# Isolation.net
KiCad netlist of a schematic drawn in Altium Designer
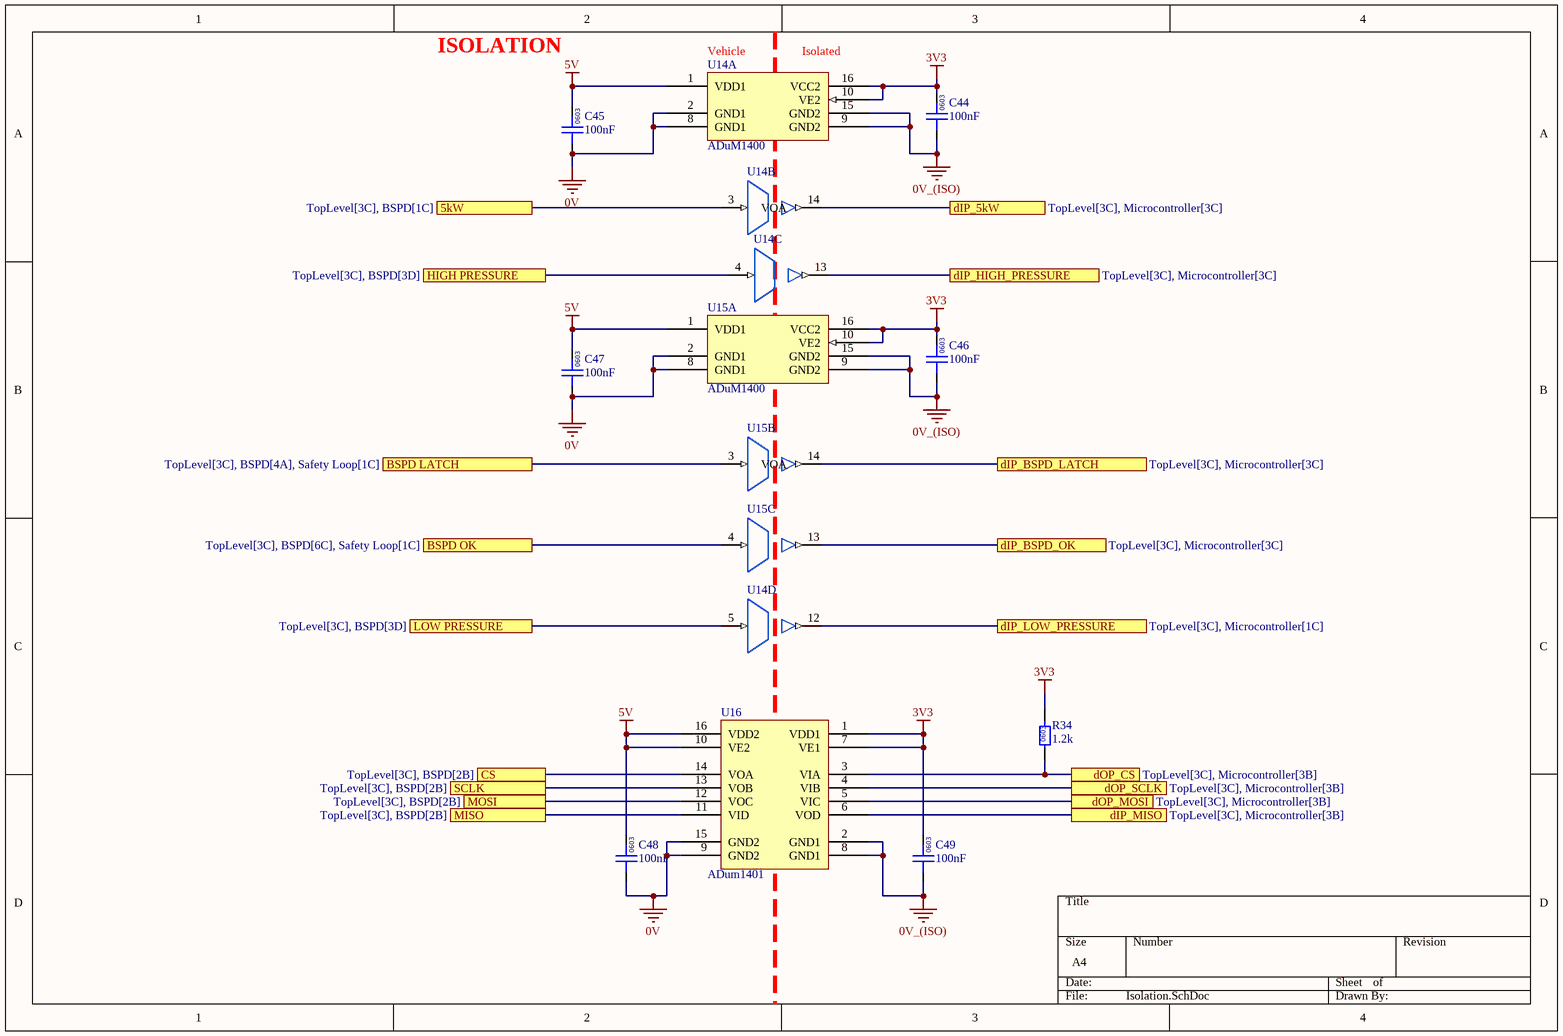
[diagram p0: Isolation.SchDoc]

(export (version "E")
  (design (tool "Eeschema 10.0.6"))
  (components
    (comp (ref "C44")
      (value "100nF")
      (footprint "0603")
      (fields
        (field (name "PART NUMBER") "GCM188L81H104KA57D")
        (field (name "MANUFACTURER") "muRata")
        (field (name "TOLERANCE") "±10%")
      )
      (libsource (lib "ts_standard_library") (part "Capacitor 0603"))
    )
    (comp (ref "C45")
      (value "100nF")
      (footprint "0603")
      (fields
        (field (name "PART NUMBER") "GCM188L81H104KA57D")
        (field (name "MANUFACTURER") "muRata")
        (field (name "TOLERANCE") "±10%")
      )
      (libsource (lib "ts_standard_library") (part "Capacitor 0603"))
    )
    (comp (ref "C46")
      (value "100nF")
      (footprint "0603")
      (fields
        (field (name "PART NUMBER") "GCM188L81H104KA57D")
        (field (name "MANUFACTURER") "muRata")
        (field (name "TOLERANCE") "±10%")
      )
      (libsource (lib "ts_standard_library") (part "Capacitor 0603"))
    )
    (comp (ref "C47")
      (value "100nF")
      (footprint "0603")
      (fields
        (field (name "PART NUMBER") "GCM188L81H104KA57D")
        (field (name "MANUFACTURER") "muRata")
        (field (name "TOLERANCE") "±10%")
      )
      (libsource (lib "ts_standard_library") (part "Capacitor 0603"))
    )
    (comp (ref "C48")
      (value "100nF")
      (footprint "0603")
      (fields
        (field (name "PART NUMBER") "GCM188L81H104KA57D")
        (field (name "MANUFACTURER") "muRata")
        (field (name "TOLERANCE") "±10%")
      )
      (libsource (lib "ts_standard_library") (part "Capacitor 0603"))
    )
    (comp (ref "C49")
      (value "100nF")
      (footprint "0603")
      (fields
        (field (name "PART NUMBER") "GCM188L81H104KA57D")
        (field (name "MANUFACTURER") "muRata")
        (field (name "TOLERANCE") "±10%")
      )
      (libsource (lib "ts_standard_library") (part "Capacitor 0603"))
    )
    (comp (ref "R34")
      (value "1.2k")
      (footprint "0603")
      (fields
        (field (name "PART NUMBER") "RC0603JR-071K2L")
        (field (name "MANUFACTURER") "YAGEO")
        (field (name "TOLERANCE") "0.01")
      )
      (libsource (lib "ts_standard_library") (part "Resistor 0603"))
    )
    (comp (ref "U14")
      (value "ADuM1400")
      (footprint "AD 16-SOIC")
      (fields
        (field (name "MANUFACTURER") "Analog Devices")
        (field (name "DIGIKEY PART NUMBER") "ADUM1400WSRWZ-ND")
      )
      (libsource (lib "ts_standard_library") (part "ADuM1400"))
    )
    (comp (ref "U15")
      (value "ADuM1400")
      (footprint "AD 16-SOIC")
      (fields
        (field (name "MANUFACTURER") "Analog Devices")
        (field (name "DIGIKEY PART NUMBER") "ADUM1400WSRWZ-ND")
      )
      (libsource (lib "ts_standard_library") (part "ADuM1400"))
    )
    (comp (ref "U16")
      (value "ADum1401")
      (footprint "AD 16-SOIC")
      (fields (field (name "PART NUMBER") "ADuM1401") (field (name "MANUFACTURER") "Analog Devices"))
      (libsource (lib "ts_standard_library") (part "ADum1401"))
    )
  )
  (nets
    (net (code "1") (name "/5kW") (class "Default")
      (node (ref "U14") (pin "3") (pinfunction "VIA_3") (pintype "input"))
    )
    (net (code "2") (name "/BSPD LATCH") (class "Default")
      (node (ref "U15") (pin "3") (pinfunction "VIA_3") (pintype "input"))
    )
    (net (code "3") (name "/BSPD OK") (class "Default")
      (node (ref "U15") (pin "4") (pinfunction "VIB_4") (pintype "input"))
    )
    (net (code "4") (name "/CS") (class "Default")
      (node (ref "U16") (pin "14") (pinfunction "VOA_14") (pintype "passive"))
    )
    (net (code "5") (name "/HIGH PRESSURE") (class "Default")
      (node (ref "U14") (pin "4") (pinfunction "VIB_4") (pintype "input"))
    )
    (net (code "6") (name "/LOW PRESSURE") (class "Default")
      (node (ref "U14") (pin "5") (pinfunction "VIC_5") (pintype "input"))
    )
    (net (code "7") (name "/MISO") (class "Default")
      (node (ref "U16") (pin "11") (pinfunction "VID_11") (pintype "passive"))
    )
    (net (code "8") (name "/MOSI") (class "Default")
      (node (ref "U16") (pin "12") (pinfunction "VOC_12") (pintype "passive"))
    )
    (net (code "9") (name "/SCLK") (class "Default")
      (node (ref "U16") (pin "13") (pinfunction "VOB_13") (pintype "passive"))
    )
    (net (code "10") (name "/dIP_5kW") (class "Default")
      (node (ref "U14") (pin "14") (pinfunction "VOA_14") (pintype "output"))
    )
    (net (code "11") (name "/dIP_BSPD_LATCH") (class "Default")
      (node (ref "U15") (pin "14") (pinfunction "VOA_14") (pintype "output"))
    )
    (net (code "12") (name "/dIP_BSPD_OK") (class "Default")
      (node (ref "U15") (pin "13") (pinfunction "VOB_13") (pintype "output"))
    )
    (net (code "13") (name "/dIP_HIGH_PRESSURE") (class "Default")
      (node (ref "U14") (pin "13") (pinfunction "VOB_13") (pintype "output"))
    )
    (net (code "14") (name "/dIP_LOW_PRESSURE") (class "Default")
      (node (ref "U14") (pin "12") (pinfunction "VOC_12") (pintype "output"))
    )
    (net (code "15") (name "/dIP_MISO") (class "Default")
      (node (ref "U16") (pin "6") (pinfunction "VOD_6") (pintype "passive"))
    )
    (net (code "16") (name "/dOP_CS") (class "Default")
      (node (ref "R34") (pin "1") (pinfunction "1_1") (pintype "passive"))
      (node (ref "U16") (pin "3") (pinfunction "VIA_3") (pintype "passive"))
    )
    (net (code "17") (name "/dOP_MOSI") (class "Default")
      (node (ref "U16") (pin "5") (pinfunction "VIC_5") (pintype "passive"))
    )
    (net (code "18") (name "/dOP_SCLK") (class "Default")
      (node (ref "U16") (pin "4") (pinfunction "VIB_4") (pintype "passive"))
    )
    (net (code "19") (name "0V") (class "Default")
      (node (ref "C45") (pin "1") (pinfunction "1_1") (pintype "passive"))
      (node (ref "C47") (pin "1") (pinfunction "1_1") (pintype "passive"))
      (node (ref "C48") (pin "1") (pinfunction "1_1") (pintype "passive"))
      (node (ref "U14") (pin "2") (pinfunction "GND1_2") (pintype "power_in"))
      (node (ref "U14") (pin "8") (pinfunction "GND1_8") (pintype "power_in"))
      (node (ref "U15") (pin "2") (pinfunction "GND1_2") (pintype "power_in"))
      (node (ref "U15") (pin "8") (pinfunction "GND1_8") (pintype "power_in"))
      (node (ref "U16") (pin "15") (pinfunction "GND2_15") (pintype "passive"))
      (node (ref "U16") (pin "9") (pinfunction "GND2_9") (pintype "passive"))
    )
    (net (code "20") (name "0V_(ISO)") (class "Default")
      (node (ref "C44") (pin "1") (pinfunction "1_1") (pintype "passive"))
      (node (ref "C46") (pin "1") (pinfunction "1_1") (pintype "passive"))
      (node (ref "C49") (pin "1") (pinfunction "1_1") (pintype "passive"))
      (node (ref "U14") (pin "15") (pinfunction "GND2_15") (pintype "power_in"))
      (node (ref "U14") (pin "9") (pinfunction "GND2_9") (pintype "power_in"))
      (node (ref "U15") (pin "15") (pinfunction "GND2_15") (pintype "power_in"))
      (node (ref "U15") (pin "9") (pinfunction "GND2_9") (pintype "power_in"))
      (node (ref "U16") (pin "2") (pinfunction "GND1_2") (pintype "passive"))
      (node (ref "U16") (pin "8") (pinfunction "GND1_8") (pintype "passive"))
    )
    (net (code "21") (name "3V3") (class "Default")
      (node (ref "C44") (pin "2") (pinfunction "2_2") (pintype "passive"))
      (node (ref "C46") (pin "2") (pinfunction "2_2") (pintype "passive"))
      (node (ref "C49") (pin "2") (pinfunction "2_2") (pintype "passive"))
      (node (ref "R34") (pin "2") (pinfunction "2_2") (pintype "passive"))
      (node (ref "U14") (pin "10") (pinfunction "VE2_10") (pintype "input"))
      (node (ref "U14") (pin "16") (pinfunction "VCC2_16") (pintype "power_in"))
      (node (ref "U15") (pin "10") (pinfunction "VE2_10") (pintype "input"))
      (node (ref "U15") (pin "16") (pinfunction "VCC2_16") (pintype "power_in"))
      (node (ref "U16") (pin "1") (pinfunction "VDD1_1") (pintype "passive"))
      (node (ref "U16") (pin "7") (pinfunction "VE1_7") (pintype "passive"))
    )
    (net (code "22") (name "5V") (class "Default")
      (node (ref "C45") (pin "2") (pinfunction "2_2") (pintype "passive"))
      (node (ref "C47") (pin "2") (pinfunction "2_2") (pintype "passive"))
      (node (ref "C48") (pin "2") (pinfunction "2_2") (pintype "passive"))
      (node (ref "U14") (pin "1") (pinfunction "VDD1_1") (pintype "power_in"))
      (node (ref "U15") (pin "1") (pinfunction "VDD1_1") (pintype "power_in"))
      (node (ref "U16") (pin "10") (pinfunction "VE2_10") (pintype "passive"))
      (node (ref "U16") (pin "16") (pinfunction "VDD2_16") (pintype "passive"))
    )
  )
)
